# DataOut.net
KiCad netlist of a schematic drawn in Altium Designer
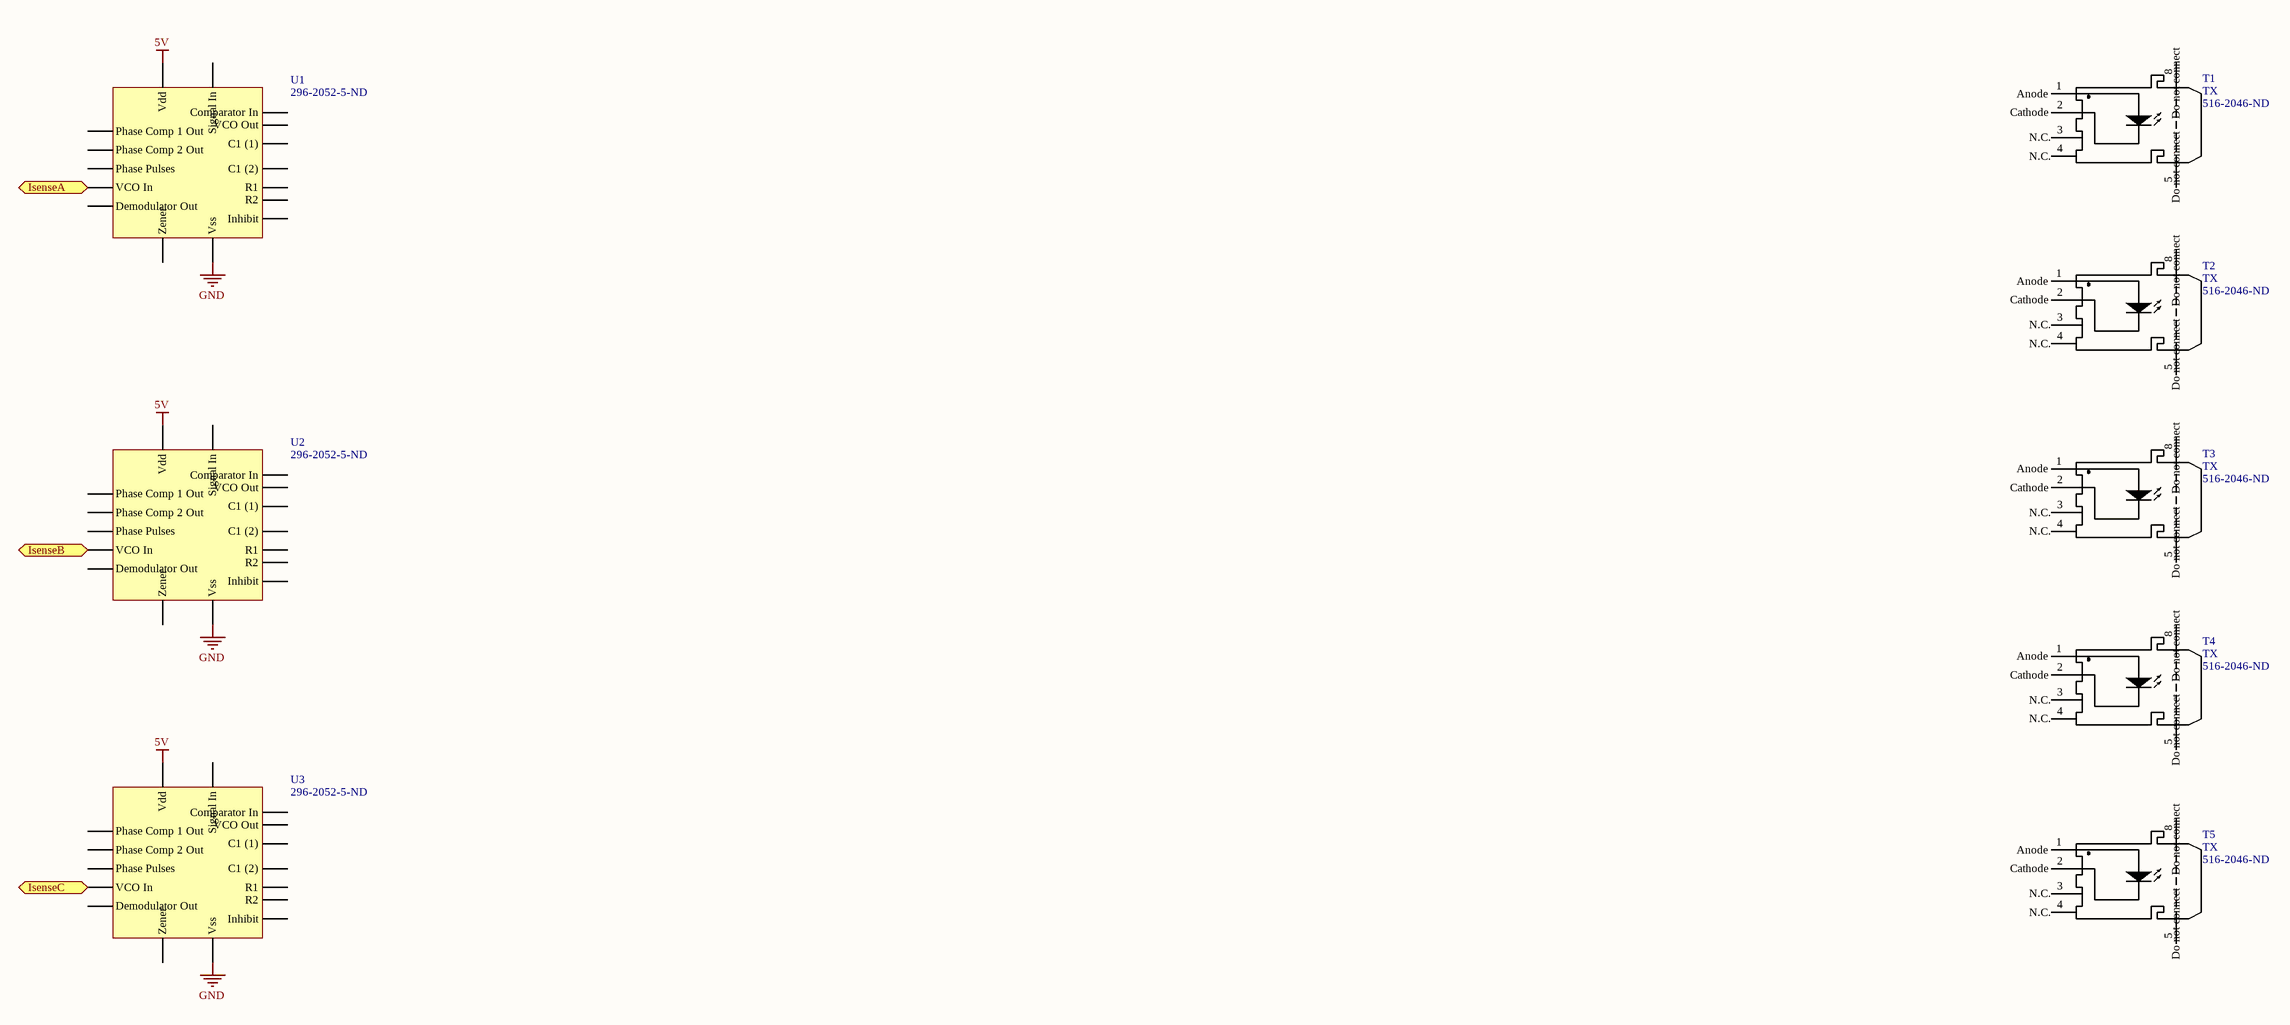
[diagram p0: DataOut.SchDoc]

(export (version "E")
  (design (tool "Eeschema 10.0.6"))
  (components
    (comp (ref "T1")
      (value "TX")
      (footprint "Optics")
      (description "Otical Transmitter")
      (fields
        (field (name "MANUFACTURER") "Broadcom Avago")
        (field (name "MANUFACTURER PART NUMBER") "HFBR-1524Z")
        (field (name "SUPPLIER PART NUMBER 1") "516-2046-ND")
      )
      (libsource (lib "T-Type Converter") (part "HFBR-1524Z"))
    )
    (comp (ref "T2")
      (value "TX")
      (footprint "Optics")
      (description "Otical Transmitter")
      (fields
        (field (name "MANUFACTURER") "Broadcom Avago")
        (field (name "MANUFACTURER PART NUMBER") "HFBR-1524Z")
        (field (name "SUPPLIER PART NUMBER 1") "516-2046-ND")
      )
      (libsource (lib "T-Type Converter") (part "HFBR-1524Z"))
    )
    (comp (ref "T3")
      (value "TX")
      (footprint "Optics")
      (description "Otical Transmitter")
      (fields
        (field (name "MANUFACTURER") "Broadcom Avago")
        (field (name "MANUFACTURER PART NUMBER") "HFBR-1524Z")
        (field (name "SUPPLIER PART NUMBER 1") "516-2046-ND")
      )
      (libsource (lib "T-Type Converter") (part "HFBR-1524Z"))
    )
    (comp (ref "T4")
      (value "TX")
      (footprint "Optics")
      (description "Otical Transmitter")
      (fields
        (field (name "MANUFACTURER") "Broadcom Avago")
        (field (name "MANUFACTURER PART NUMBER") "HFBR-1524Z")
        (field (name "SUPPLIER PART NUMBER 1") "516-2046-ND")
      )
      (libsource (lib "T-Type Converter") (part "HFBR-1524Z"))
    )
    (comp (ref "T5")
      (value "TX")
      (footprint "Optics")
      (description "Otical Transmitter")
      (fields
        (field (name "MANUFACTURER") "Broadcom Avago")
        (field (name "MANUFACTURER PART NUMBER") "HFBR-1524Z")
        (field (name "SUPPLIER PART NUMBER 1") "516-2046-ND")
      )
      (libsource (lib "T-Type Converter") (part "HFBR-1524Z"))
    )
    (comp (ref "U1")
      (value "CD4046B")
      (footprint "DIP16")
      (description "VCO")
      (fields
        (field (name "MANUFACTURER") "Texas Instruments")
        (field (name "MANUFACTURER PART NUMBER") "CD4046BE")
        (field (name "SUPPLIER PART NUMBER 1") "296-2052-5-ND")
      )
      (libsource (lib "T-Type Converter") (part "CD4046B"))
    )
    (comp (ref "U2")
      (value "CD4046B")
      (footprint "DIP16")
      (description "VCO")
      (fields
        (field (name "MANUFACTURER") "Texas Instruments")
        (field (name "MANUFACTURER PART NUMBER") "CD4046BE")
        (field (name "SUPPLIER PART NUMBER 1") "296-2052-5-ND")
      )
      (libsource (lib "T-Type Converter") (part "CD4046B"))
    )
    (comp (ref "U3")
      (value "CD4046B")
      (footprint "DIP16")
      (description "VCO")
      (fields
        (field (name "MANUFACTURER") "Texas Instruments")
        (field (name "MANUFACTURER PART NUMBER") "CD4046BE")
        (field (name "SUPPLIER PART NUMBER 1") "296-2052-5-ND")
      )
      (libsource (lib "T-Type Converter") (part "CD4046B"))
    )
  )
  (nets
    (net (code "1") (name "/IsenseA") (class "Default")
      (node (ref "U1") (pin "9") (pinfunction "VCO_In_9") (pintype "passive"))
    )
    (net (code "2") (name "/IsenseB") (class "Default")
      (node (ref "U2") (pin "9") (pinfunction "VCO_In_9") (pintype "passive"))
    )
    (net (code "3") (name "/IsenseC") (class "Default")
      (node (ref "U3") (pin "9") (pinfunction "VCO_In_9") (pintype "passive"))
    )
    (net (code "4") (name "5V") (class "Default")
      (node (ref "U1") (pin "16") (pinfunction "Vdd_16") (pintype "passive"))
      (node (ref "U2") (pin "16") (pinfunction "Vdd_16") (pintype "passive"))
      (node (ref "U3") (pin "16") (pinfunction "Vdd_16") (pintype "passive"))
    )
    (net (code "5") (name "GND") (class "Default")
      (node (ref "U1") (pin "8") (pinfunction "Vss_8") (pintype "passive"))
      (node (ref "U2") (pin "8") (pinfunction "Vss_8") (pintype "passive"))
      (node (ref "U3") (pin "8") (pinfunction "Vss_8") (pintype "passive"))
    )
    (net (code "6") (name "unconnected-(T1-Anode-Pad1)") (class "Default")
      (node (ref "T1") (pin "1") (pinfunction "Anode_1") (pintype "passive"))
    )
    (net (code "7") (name "unconnected-(T1-Cathode-Pad2)") (class "Default")
      (node (ref "T1") (pin "2") (pinfunction "Cathode_2") (pintype "passive"))
    )
    (net (code "8") (name "unconnected-(T1-Do_not_connect-Pad5)") (class "Default")
      (node (ref "T1") (pin "5") (pinfunction "Do_not_connect_5") (pintype "passive"))
    )
    (net (code "9") (name "unconnected-(T1-Do_not_connect-Pad8)") (class "Default")
      (node (ref "T1") (pin "8") (pinfunction "Do_not_connect_8") (pintype "passive"))
    )
    (net (code "10") (name "unconnected-(T1-N.C.-Pad3)") (class "Default")
      (node (ref "T1") (pin "3") (pinfunction "N.C._3") (pintype "passive"))
    )
    (net (code "11") (name "unconnected-(T1-N.C.-Pad4)") (class "Default")
      (node (ref "T1") (pin "4") (pinfunction "N.C._4") (pintype "passive"))
    )
    (net (code "12") (name "unconnected-(T2-Anode-Pad1)") (class "Default")
      (node (ref "T2") (pin "1") (pinfunction "Anode_1") (pintype "passive"))
    )
    (net (code "13") (name "unconnected-(T2-Cathode-Pad2)") (class "Default")
      (node (ref "T2") (pin "2") (pinfunction "Cathode_2") (pintype "passive"))
    )
    (net (code "14") (name "unconnected-(T2-Do_not_connect-Pad5)") (class "Default")
      (node (ref "T2") (pin "5") (pinfunction "Do_not_connect_5") (pintype "passive"))
    )
    (net (code "15") (name "unconnected-(T2-Do_not_connect-Pad8)") (class "Default")
      (node (ref "T2") (pin "8") (pinfunction "Do_not_connect_8") (pintype "passive"))
    )
    (net (code "16") (name "unconnected-(T2-N.C.-Pad3)") (class "Default")
      (node (ref "T2") (pin "3") (pinfunction "N.C._3") (pintype "passive"))
    )
    (net (code "17") (name "unconnected-(T2-N.C.-Pad4)") (class "Default")
      (node (ref "T2") (pin "4") (pinfunction "N.C._4") (pintype "passive"))
    )
    (net (code "18") (name "unconnected-(T3-Anode-Pad1)") (class "Default")
      (node (ref "T3") (pin "1") (pinfunction "Anode_1") (pintype "passive"))
    )
    (net (code "19") (name "unconnected-(T3-Cathode-Pad2)") (class "Default")
      (node (ref "T3") (pin "2") (pinfunction "Cathode_2") (pintype "passive"))
    )
    (net (code "20") (name "unconnected-(T3-Do_not_connect-Pad5)") (class "Default")
      (node (ref "T3") (pin "5") (pinfunction "Do_not_connect_5") (pintype "passive"))
    )
    (net (code "21") (name "unconnected-(T3-Do_not_connect-Pad8)") (class "Default")
      (node (ref "T3") (pin "8") (pinfunction "Do_not_connect_8") (pintype "passive"))
    )
    (net (code "22") (name "unconnected-(T3-N.C.-Pad3)") (class "Default")
      (node (ref "T3") (pin "3") (pinfunction "N.C._3") (pintype "passive"))
    )
    (net (code "23") (name "unconnected-(T3-N.C.-Pad4)") (class "Default")
      (node (ref "T3") (pin "4") (pinfunction "N.C._4") (pintype "passive"))
    )
    (net (code "24") (name "unconnected-(T4-Anode-Pad1)") (class "Default")
      (node (ref "T4") (pin "1") (pinfunction "Anode_1") (pintype "passive"))
    )
    (net (code "25") (name "unconnected-(T4-Cathode-Pad2)") (class "Default")
      (node (ref "T4") (pin "2") (pinfunction "Cathode_2") (pintype "passive"))
    )
    (net (code "26") (name "unconnected-(T4-Do_not_connect-Pad5)") (class "Default")
      (node (ref "T4") (pin "5") (pinfunction "Do_not_connect_5") (pintype "passive"))
    )
    (net (code "27") (name "unconnected-(T4-Do_not_connect-Pad8)") (class "Default")
      (node (ref "T4") (pin "8") (pinfunction "Do_not_connect_8") (pintype "passive"))
    )
    (net (code "28") (name "unconnected-(T4-N.C.-Pad3)") (class "Default")
      (node (ref "T4") (pin "3") (pinfunction "N.C._3") (pintype "passive"))
    )
    (net (code "29") (name "unconnected-(T4-N.C.-Pad4)") (class "Default")
      (node (ref "T4") (pin "4") (pinfunction "N.C._4") (pintype "passive"))
    )
    (net (code "30") (name "unconnected-(T5-Anode-Pad1)") (class "Default")
      (node (ref "T5") (pin "1") (pinfunction "Anode_1") (pintype "passive"))
    )
    (net (code "31") (name "unconnected-(T5-Cathode-Pad2)") (class "Default")
      (node (ref "T5") (pin "2") (pinfunction "Cathode_2") (pintype "passive"))
    )
    (net (code "32") (name "unconnected-(T5-Do_not_connect-Pad5)") (class "Default")
      (node (ref "T5") (pin "5") (pinfunction "Do_not_connect_5") (pintype "passive"))
    )
    (net (code "33") (name "unconnected-(T5-Do_not_connect-Pad8)") (class "Default")
      (node (ref "T5") (pin "8") (pinfunction "Do_not_connect_8") (pintype "passive"))
    )
    (net (code "34") (name "unconnected-(T5-N.C.-Pad3)") (class "Default")
      (node (ref "T5") (pin "3") (pinfunction "N.C._3") (pintype "passive"))
    )
    (net (code "35") (name "unconnected-(T5-N.C.-Pad4)") (class "Default")
      (node (ref "T5") (pin "4") (pinfunction "N.C._4") (pintype "passive"))
    )
    (net (code "36") (name "unconnected-(U1-C1_(1)-Pad6)") (class "Default")
      (node (ref "U1") (pin "6") (pinfunction "C1_(1)_6") (pintype "passive"))
    )
    (net (code "37") (name "unconnected-(U1-C1_(2)-Pad7)") (class "Default")
      (node (ref "U1") (pin "7") (pinfunction "C1_(2)_7") (pintype "passive"))
    )
    (net (code "38") (name "unconnected-(U1-Comparator_In-Pad3)") (class "Default")
      (node (ref "U1") (pin "3") (pinfunction "Comparator_In_3") (pintype "passive"))
    )
    (net (code "39") (name "unconnected-(U1-Demodulator_Out-Pad10)") (class "Default")
      (node (ref "U1") (pin "10") (pinfunction "Demodulator_Out_10") (pintype "passive"))
    )
    (net (code "40") (name "unconnected-(U1-Inhibit-Pad5)") (class "Default")
      (node (ref "U1") (pin "5") (pinfunction "Inhibit_5") (pintype "passive"))
    )
    (net (code "41") (name "unconnected-(U1-Phase_Comp_1_Out-Pad2)") (class "Default")
      (node (ref "U1") (pin "2") (pinfunction "Phase_Comp_1_Out_2") (pintype "passive"))
    )
    (net (code "42") (name "unconnected-(U1-Phase_Comp_2_Out-Pad13)") (class "Default")
      (node (ref "U1") (pin "13") (pinfunction "Phase_Comp_2_Out_13") (pintype "passive"))
    )
    (net (code "43") (name "unconnected-(U1-Phase_Pulses-Pad1)") (class "Default")
      (node (ref "U1") (pin "1") (pinfunction "Phase_Pulses_1") (pintype "passive"))
    )
    (net (code "44") (name "unconnected-(U1-R1-Pad11)") (class "Default")
      (node (ref "U1") (pin "11") (pinfunction "R1_11") (pintype "passive"))
    )
    (net (code "45") (name "unconnected-(U1-R2-Pad12)") (class "Default")
      (node (ref "U1") (pin "12") (pinfunction "R2_12") (pintype "passive"))
    )
    (net (code "46") (name "unconnected-(U1-Signal_In-Pad14)") (class "Default")
      (node (ref "U1") (pin "14") (pinfunction "Signal_In_14") (pintype "passive"))
    )
    (net (code "47") (name "unconnected-(U1-VCO_Out-Pad4)") (class "Default")
      (node (ref "U1") (pin "4") (pinfunction "VCO_Out_4") (pintype "passive"))
    )
    (net (code "48") (name "unconnected-(U1-Zener-Pad15)") (class "Default")
      (node (ref "U1") (pin "15") (pinfunction "Zener_15") (pintype "passive"))
    )
    (net (code "49") (name "unconnected-(U2-C1_(1)-Pad6)") (class "Default")
      (node (ref "U2") (pin "6") (pinfunction "C1_(1)_6") (pintype "passive"))
    )
    (net (code "50") (name "unconnected-(U2-C1_(2)-Pad7)") (class "Default")
      (node (ref "U2") (pin "7") (pinfunction "C1_(2)_7") (pintype "passive"))
    )
    (net (code "51") (name "unconnected-(U2-Comparator_In-Pad3)") (class "Default")
      (node (ref "U2") (pin "3") (pinfunction "Comparator_In_3") (pintype "passive"))
    )
    (net (code "52") (name "unconnected-(U2-Demodulator_Out-Pad10)") (class "Default")
      (node (ref "U2") (pin "10") (pinfunction "Demodulator_Out_10") (pintype "passive"))
    )
    (net (code "53") (name "unconnected-(U2-Inhibit-Pad5)") (class "Default")
      (node (ref "U2") (pin "5") (pinfunction "Inhibit_5") (pintype "passive"))
    )
    (net (code "54") (name "unconnected-(U2-Phase_Comp_1_Out-Pad2)") (class "Default")
      (node (ref "U2") (pin "2") (pinfunction "Phase_Comp_1_Out_2") (pintype "passive"))
    )
    (net (code "55") (name "unconnected-(U2-Phase_Comp_2_Out-Pad13)") (class "Default")
      (node (ref "U2") (pin "13") (pinfunction "Phase_Comp_2_Out_13") (pintype "passive"))
    )
    (net (code "56") (name "unconnected-(U2-Phase_Pulses-Pad1)") (class "Default")
      (node (ref "U2") (pin "1") (pinfunction "Phase_Pulses_1") (pintype "passive"))
    )
    (net (code "57") (name "unconnected-(U2-R1-Pad11)") (class "Default")
      (node (ref "U2") (pin "11") (pinfunction "R1_11") (pintype "passive"))
    )
    (net (code "58") (name "unconnected-(U2-R2-Pad12)") (class "Default")
      (node (ref "U2") (pin "12") (pinfunction "R2_12") (pintype "passive"))
    )
    (net (code "59") (name "unconnected-(U2-Signal_In-Pad14)") (class "Default")
      (node (ref "U2") (pin "14") (pinfunction "Signal_In_14") (pintype "passive"))
    )
    (net (code "60") (name "unconnected-(U2-VCO_Out-Pad4)") (class "Default")
      (node (ref "U2") (pin "4") (pinfunction "VCO_Out_4") (pintype "passive"))
    )
    (net (code "61") (name "unconnected-(U2-Zener-Pad15)") (class "Default")
      (node (ref "U2") (pin "15") (pinfunction "Zener_15") (pintype "passive"))
    )
    (net (code "62") (name "unconnected-(U3-C1_(1)-Pad6)") (class "Default")
      (node (ref "U3") (pin "6") (pinfunction "C1_(1)_6") (pintype "passive"))
    )
    (net (code "63") (name "unconnected-(U3-C1_(2)-Pad7)") (class "Default")
      (node (ref "U3") (pin "7") (pinfunction "C1_(2)_7") (pintype "passive"))
    )
    (net (code "64") (name "unconnected-(U3-Comparator_In-Pad3)") (class "Default")
      (node (ref "U3") (pin "3") (pinfunction "Comparator_In_3") (pintype "passive"))
    )
    (net (code "65") (name "unconnected-(U3-Demodulator_Out-Pad10)") (class "Default")
      (node (ref "U3") (pin "10") (pinfunction "Demodulator_Out_10") (pintype "passive"))
    )
    (net (code "66") (name "unconnected-(U3-Inhibit-Pad5)") (class "Default")
      (node (ref "U3") (pin "5") (pinfunction "Inhibit_5") (pintype "passive"))
    )
    (net (code "67") (name "unconnected-(U3-Phase_Comp_1_Out-Pad2)") (class "Default")
      (node (ref "U3") (pin "2") (pinfunction "Phase_Comp_1_Out_2") (pintype "passive"))
    )
    (net (code "68") (name "unconnected-(U3-Phase_Comp_2_Out-Pad13)") (class "Default")
      (node (ref "U3") (pin "13") (pinfunction "Phase_Comp_2_Out_13") (pintype "passive"))
    )
    (net (code "69") (name "unconnected-(U3-Phase_Pulses-Pad1)") (class "Default")
      (node (ref "U3") (pin "1") (pinfunction "Phase_Pulses_1") (pintype "passive"))
    )
    (net (code "70") (name "unconnected-(U3-R1-Pad11)") (class "Default")
      (node (ref "U3") (pin "11") (pinfunction "R1_11") (pintype "passive"))
    )
    (net (code "71") (name "unconnected-(U3-R2-Pad12)") (class "Default")
      (node (ref "U3") (pin "12") (pinfunction "R2_12") (pintype "passive"))
    )
    (net (code "72") (name "unconnected-(U3-Signal_In-Pad14)") (class "Default")
      (node (ref "U3") (pin "14") (pinfunction "Signal_In_14") (pintype "passive"))
    )
    (net (code "73") (name "unconnected-(U3-VCO_Out-Pad4)") (class "Default")
      (node (ref "U3") (pin "4") (pinfunction "VCO_Out_4") (pintype "passive"))
    )
    (net (code "74") (name "unconnected-(U3-Zener-Pad15)") (class "Default")
      (node (ref "U3") (pin "15") (pinfunction "Zener_15") (pintype "passive"))
    )
  )
)
